# alimentation.net
KiCad netlist of a schematic drawn in Altium Designer
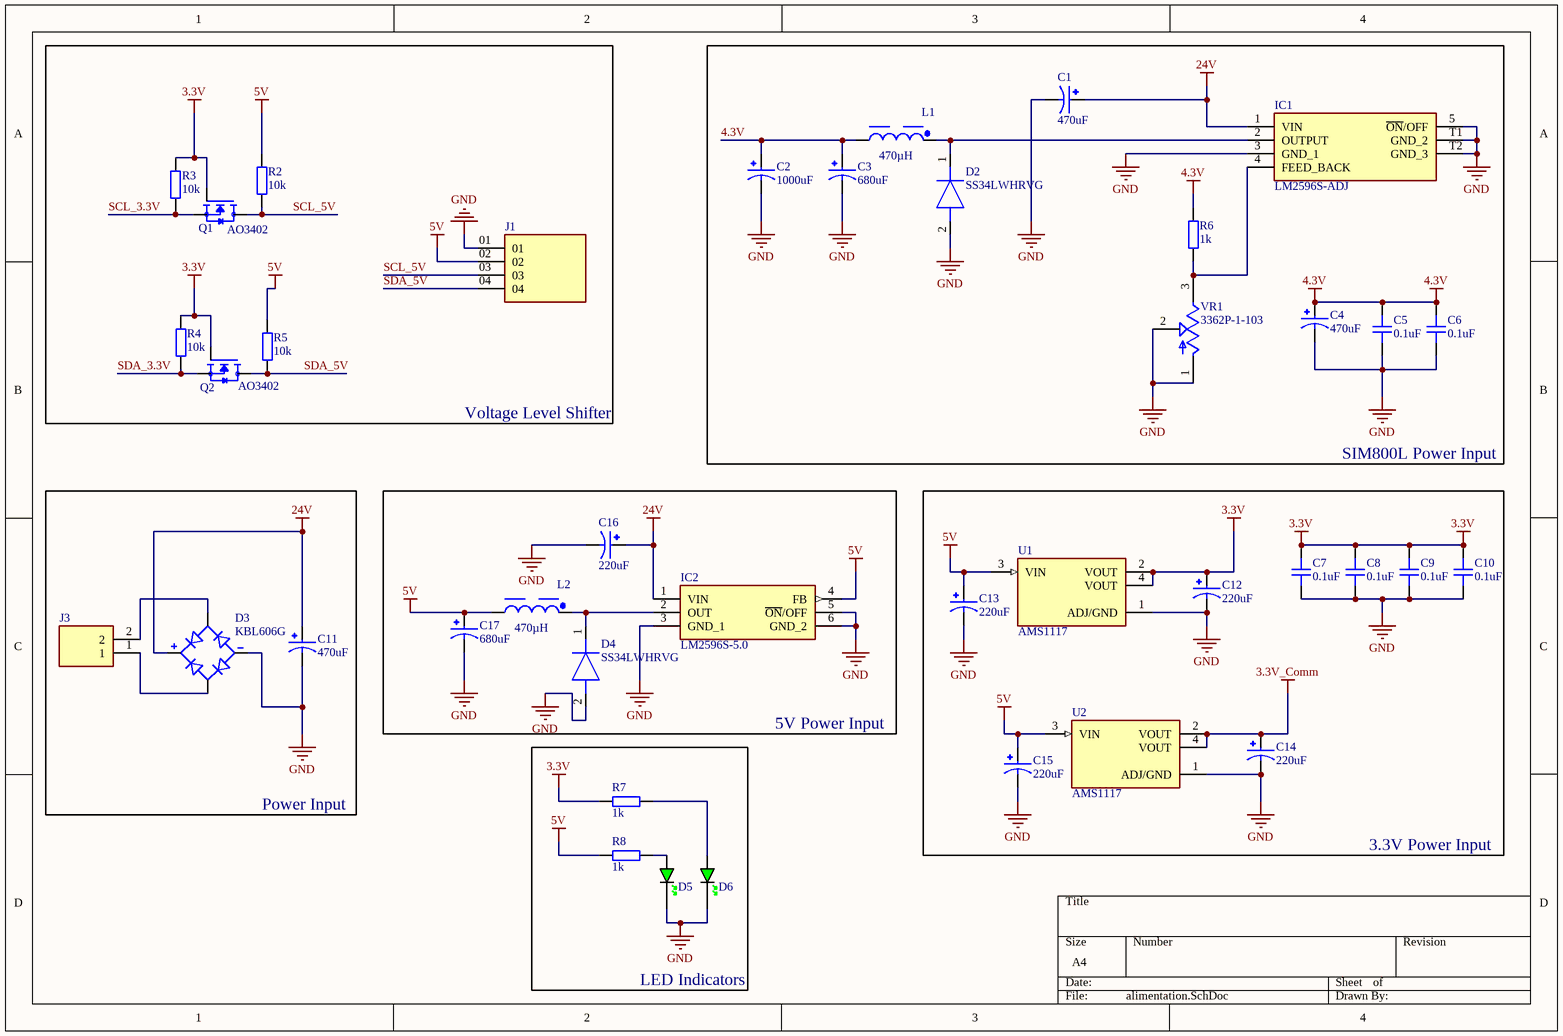
[diagram p0: alimentation.SchDoc]

(export (version "E")
  (design (tool "Eeschema 10.0.6"))
  (components
    (comp (ref "C1")
      (value "470uF")
      (footprint "CAPPRD500W60D1000H1600")
      (description "CAP ALUM 680UF 20% 35V RADIAL")
      (fields (field (name "MF") "Panasonic") (field (name "MP") "EEU-HD1V681B"))
      (libsource (lib "") (part "EEUHD1V681B_1"))
    )
    (comp (ref "C2")
      (value "1000uF")
      (footprint "CAPPRD500W60D1000H2500")
      (description "1000ÂµF 35V Aluminum Electrolytic Capacitors Radial, Can 10000 Hrs @ 105Â°C")
      (fields (field (name "MP") "EEUFS1V102L") (field (name "MF") "Panasonic"))
      (libsource (lib "1000uF 35V capacitor") (part "EEUFS1V102L"))
    )
    (comp (ref "C3")
      (value "680uF")
      (footprint "CAPPRD500W60D1000H1600")
      (description "CAP ALUM 680UF 20% 35V RADIAL")
      (fields (field (name "MF") "Panasonic") (field (name "MP") "EEU-HD1V681B"))
      (libsource (lib "35V 680uF cap") (part "EEUHD1V681B"))
    )
    (comp (ref "C4")
      (value "470uF")
      (footprint "CAPPRD500W60D1000H1600")
      (description "CAP ALUM 680UF 20% 35V RADIAL")
      (fields (field (name "MF") "Panasonic") (field (name "MP") "EEU-HD1V681B"))
      (libsource (lib "35V 680uF cap") (part "EEUHD1V681B"))
    )
    (comp (ref "C5")
      (value "0.1uF")
      (footprint "CAP_0805")
      (description "Capacitor SMD 0805")
      (libsource (lib "Schematic-Lib-PhilsLab") (part "CAP_0805"))
    )
    (comp (ref "C6")
      (value "0.1uF")
      (footprint "CAP_0805")
      (description "Capacitor SMD 0805")
      (libsource (lib "Schematic-Lib-PhilsLab") (part "CAP_0805"))
    )
    (comp (ref "C7")
      (value "0.1uF")
      (footprint "CAP_0805")
      (description "Capacitor SMD 0805")
      (libsource (lib "Schematic-Lib-PhilsLab") (part "CAP_0805"))
    )
    (comp (ref "C8")
      (value "0.1uF")
      (footprint "CAP_0805")
      (description "Capacitor SMD 0805")
      (libsource (lib "Schematic-Lib-PhilsLab") (part "CAP_0805"))
    )
    (comp (ref "C9")
      (value "0.1uF")
      (footprint "CAP_0805")
      (description "Capacitor SMD 0805")
      (libsource (lib "Schematic-Lib-PhilsLab") (part "CAP_0805"))
    )
    (comp (ref "C10")
      (value "0.1uF")
      (footprint "CAP_0805")
      (description "Capacitor SMD 0805")
      (libsource (lib "Schematic-Lib-PhilsLab") (part "CAP_0805"))
    )
    (comp (ref "C11")
      (value "470uF")
      (footprint "CAPPRD500W60D1000H1600")
      (description "CAP ALUM 680UF 20% 35V RADIAL")
      (fields (field (name "MF") "Panasonic") (field (name "MP") "EEU-HD1V681B"))
      (libsource (lib "35V 680uF cap") (part "EEUHD1V681B"))
    )
    (comp (ref "C12")
      (value "220uF")
      (footprint "CAPPRD500W60D800H1150")
      (description "Cap Aluminum 220uF 35V 20% (8 X 11.5mm) Radial 5mm 270mA 1000 hr 105C Ammo Pack")
      (fields (field (name "MP") "EEU-HD1V221B") (field (name "MF") "Panasonic"))
      (libsource (lib "35V 220uF cap") (part "EEUHD1V221B"))
    )
    (comp (ref "C13")
      (value "220uF")
      (footprint "CAPPRD500W60D800H1150")
      (description "Cap Aluminum 220uF 35V 20% (8 X 11.5mm) Radial 5mm 270mA 1000 hr 105C Ammo Pack")
      (fields (field (name "MP") "EEU-HD1V221B") (field (name "MF") "Panasonic"))
      (libsource (lib "35V 220uF cap") (part "EEUHD1V221B"))
    )
    (comp (ref "C14")
      (value "220uF")
      (footprint "CAPPRD500W60D800H1150")
      (description "Cap Aluminum 220uF 35V 20% (8 X 11.5mm) Radial 5mm 270mA 1000 hr 105C Ammo Pack")
      (fields (field (name "MP") "EEU-HD1V221B") (field (name "MF") "Panasonic"))
      (libsource (lib "35V 220uF cap") (part "EEUHD1V221B"))
    )
    (comp (ref "C15")
      (value "220uF")
      (footprint "CAPPRD500W60D800H1150")
      (description "Cap Aluminum 220uF 35V 20% (8 X 11.5mm) Radial 5mm 270mA 1000 hr 105C Ammo Pack")
      (fields (field (name "MP") "EEU-HD1V221B") (field (name "MF") "Panasonic"))
      (libsource (lib "35V 220uF cap") (part "EEUHD1V221B"))
    )
    (comp (ref "C16")
      (value "220uF")
      (footprint "CAPPRD500W60D800H1150")
      (description "Cap Aluminum 220uF 35V 20% (8 X 11.5mm) Radial 5mm 270mA 1000 hr 105C Ammo Pack")
      (fields (field (name "MP") "EEU-HD1V221B") (field (name "MF") "Panasonic"))
      (libsource (lib "") (part "EEUHD1V221B_1"))
    )
    (comp (ref "C17")
      (value "680uF")
      (footprint "CAPPRD500W60D1000H1600")
      (description "CAP ALUM 680UF 20% 35V RADIAL")
      (fields (field (name "MF") "Panasonic") (field (name "MP") "EEU-HD1V681B"))
      (libsource (lib "35V 680uF cap") (part "EEUHD1V681B"))
    )
    (comp (ref "D2")
      (value "SS34LWHRVG")
      (footprint "SamacSys:SODFL3718X102N")
      (description "Diode")
      (fields (field (name "MOUSER PART NUMBER") "821-SS34LWHRVG"))
      (libsource (lib "*") (part "SS34LWHRVG"))
    )
    (comp (ref "D3")
      (value "KBL606G")
      (footprint "SIP600W130P510L1900H1630Q4")
      (libsource (lib "KBL606G") (part "KBL606G"))
    )
    (comp (ref "D4")
      (value "SS34LWHRVG")
      (footprint "SamacSys:SODFL3718X102N")
      (description "Diode")
      (fields (field (name "MOUSER PART NUMBER") "821-SS34LWHRVG"))
      (libsource (lib "*") (part "SS34LWHRVG"))
    )
    (comp (ref "D5")
      (value "GREEN")
      (footprint "LED_0805_GREEN")
      (description "LED 0805 GREEN SMD")
      (libsource (lib "Schematic-Lib-PhilsLab") (part "LED_0805_GREEN"))
    )
    (comp (ref "D6")
      (value "GREEN")
      (footprint "LED_0805_GREEN")
      (description "LED 0805 GREEN SMD")
      (libsource (lib "Schematic-Lib-PhilsLab") (part "LED_0805_GREEN"))
    )
    (comp (ref "IC1")
      (value "LM2596S-ADJ")
      (footprint "SamacSys:LM2596SXADJ")
      (description "Integrated Circuit")
      (fields (field (name "MOUSER PART NUMBER") "926-LM2596S-ADJ"))
      (libsource (lib "*") (part "LM2596S-ADJ"))
    )
    (comp (ref "IC2")
      (value "LM2596S-5.0")
      (footprint "SamacSys:KTT0005B")
      (description "Integrated Circuit")
      (fields (field (name "MOUSER PART NUMBER") "926-LM2596S-50"))
      (libsource (lib "*") (part "LM2596S-5.0"))
    )
    (comp (ref "J1")
      (value "MTSW-104-08-S-S-270")
      (footprint "SAMTEC_MTSW-104-08-S-S-270")
      (description "Connector Header Through Hole 4 position 0.100 (2.54mm)")
      (fields (field (name "MF") "Samtec"))
      (libsource (lib "TH 4 pins header") (part "MTSW-104-08-S-S-270"))
    )
    (comp (ref "J3")
      (value "TBP04R12-500-02BE")
      (footprint "CUI_TBP04R12-500-02BE")
      (description "2~24 Poles, Pluggable, Receptacle, Horizontal, 5.0 Pitch, Terminal Block Connector")
      (fields (field (name "MF") "Same Sky"))
      (libsource (lib "TBP04R12-500-02BE") (part "TBP04R12-500-02BE"))
    )
    (comp (ref "L1")
      (value "470µH")
      (footprint "WE-PD HV_1210")
      (description "WE-PD HV High Voltage Power Inductor, SMT, size 1210, 1000µH, 0.72A, 1.4Ω")
      (fields
        (field (name "MANUFACTURER PART NUMBER") "7687709102")
        (field (name "MANUFACTURER") "Wurth Elektronik")
      )
      (libsource (lib "inductors") (part "7687709102"))
    )
    (comp (ref "L2")
      (value "470µH")
      (footprint "WE-PD HV_1210")
      (description "WE-PD HV High Voltage Power Inductor, SMT, size 1210, 1000µH, 0.72A, 1.4Ω")
      (fields
        (field (name "MANUFACTURER PART NUMBER") "7687709102")
        (field (name "MANUFACTURER") "Wurth Elektronik")
      )
      (libsource (lib "inductors") (part "7687709102"))
    )
    (comp (ref "Q1")
      (value "AO3402")
      (footprint "SOT95P280X125-3N")
      (description "N-Channel 30 V 4A (Ta) 1.4W (Ta) Surface Mount SOT-23-3")
      (fields (field (name "MF") "Alpha & Omega Semiconductor"))
      (libsource (lib "AO3402") (part "AO3402"))
    )
    (comp (ref "Q2")
      (value "AO3402")
      (footprint "SOT95P280X125-3N")
      (description "N-Channel 30 V 4A (Ta) 1.4W (Ta) Surface Mount SOT-23-3")
      (fields (field (name "MF") "Alpha & Omega Semiconductor"))
      (libsource (lib "AO3402") (part "AO3402"))
    )
    (comp (ref "R2")
      (value "10k")
      (footprint "RES_1206")
      (description "Resistor SMD 1206")
      (libsource (lib "Schematic-Lib-PhilsLab") (part "RES_1206"))
    )
    (comp (ref "R3")
      (value "10k")
      (footprint "RES_1206")
      (description "Resistor SMD 1206")
      (libsource (lib "Schematic-Lib-PhilsLab") (part "RES_1206"))
    )
    (comp (ref "R4")
      (value "10k")
      (footprint "RES_1206")
      (description "Resistor SMD 1206")
      (libsource (lib "Schematic-Lib-PhilsLab") (part "RES_1206"))
    )
    (comp (ref "R5")
      (value "10k")
      (footprint "RES_1206")
      (description "Resistor SMD 1206")
      (libsource (lib "Schematic-Lib-PhilsLab") (part "RES_1206"))
    )
    (comp (ref "R6")
      (value "1k")
      (footprint "RES_1206")
      (description "Resistor SMD 1206")
      (libsource (lib "Schematic-Lib-PhilsLab") (part "RES_1206"))
    )
    (comp (ref "R7")
      (value "1k")
      (footprint "RES_1206")
      (description "Resistor SMD 1206")
      (libsource (lib "Schematic-Lib-PhilsLab") (part "RES_1206"))
    )
    (comp (ref "R8")
      (value "1k")
      (footprint "RES_1206")
      (description "Resistor SMD 1206")
      (libsource (lib "Schematic-Lib-PhilsLab") (part "RES_1206"))
    )
    (comp (ref "U1")
      (value "AMS1117")
      (footprint "SOT229P700X180-4N")
      (description "1A LOW DROPOUT VOLTAGE REGULATOR SOT-223")
      (fields (field (name "MF") "Advanced Monolithic Systems"))
      (libsource (lib "AMS1117") (part "AMS1117"))
    )
    (comp (ref "U2")
      (value "AMS1117")
      (footprint "SOT229P700X180-4N")
      (description "1A LOW DROPOUT VOLTAGE REGULATOR SOT-223")
      (fields (field (name "MF") "Advanced Monolithic Systems"))
      (libsource (lib "AMS1117") (part "AMS1117"))
    )
    (comp (ref "VR1")
      (value "3362P-1-103")
      (footprint "TRIM_3362P-1-103:TRIM_3362P-1-103")
      (description "TRIMMER - 1/4in SQ ST CERMET ¦ Bourns 3362P-1-103")
      (fields (field (name "MF") "Bourns"))
      (libsource (lib "3362P-1-103") (part "3362P-1-103"))
    )
  )
  (nets
    (net (code "1") (name "/SCL_3.3V") (class "Default")
      (node (ref "Q1") (pin "2") (pinfunction "S_2") (pintype "passive"))
      (node (ref "R3") (pin "2") (pinfunction "2_2") (pintype "passive"))
    )
    (net (code "2") (name "/SCL_5V") (class "Default")
      (node (ref "J1") (pin "03") (pinfunction "03_03") (pintype "passive"))
      (node (ref "Q1") (pin "3") (pinfunction "D_3") (pintype "passive"))
      (node (ref "R2") (pin "2") (pinfunction "2_2") (pintype "passive"))
    )
    (net (code "3") (name "/SDA_3.3V") (class "Default")
      (node (ref "Q2") (pin "2") (pinfunction "S_2") (pintype "passive"))
      (node (ref "R4") (pin "2") (pinfunction "2_2") (pintype "passive"))
    )
    (net (code "4") (name "/SDA_5V") (class "Default")
      (node (ref "J1") (pin "04") (pinfunction "04_04") (pintype "passive"))
      (node (ref "Q2") (pin "3") (pinfunction "D_3") (pintype "passive"))
      (node (ref "R5") (pin "2") (pinfunction "2_2") (pintype "passive"))
    )
    (net (code "5") (name "3.3V") (class "Default")
      (node (ref "C10") (pin "2") (pinfunction "2_2") (pintype "passive"))
      (node (ref "C12") (pin "P") (pinfunction "P_P") (pintype "passive"))
      (node (ref "C7") (pin "2") (pinfunction "2_2") (pintype "passive"))
      (node (ref "C8") (pin "2") (pinfunction "2_2") (pintype "passive"))
      (node (ref "C9") (pin "2") (pinfunction "2_2") (pintype "passive"))
      (node (ref "Q1") (pin "1") (pinfunction "G_1") (pintype "passive"))
      (node (ref "Q2") (pin "1") (pinfunction "G_1") (pintype "passive"))
      (node (ref "R3") (pin "1") (pinfunction "1_1") (pintype "passive"))
      (node (ref "R4") (pin "1") (pinfunction "1_1") (pintype "passive"))
      (node (ref "R7") (pin "1") (pinfunction "1_1") (pintype "passive"))
      (node (ref "U1") (pin "2") (pinfunction "VOUT_2") (pintype "power_in"))
      (node (ref "U1") (pin "4") (pinfunction "VOUT_4") (pintype "power_in"))
    )
    (net (code "6") (name "3.3V_Comm") (class "Default")
      (node (ref "C14") (pin "P") (pinfunction "P_P") (pintype "passive"))
      (node (ref "U2") (pin "2") (pinfunction "VOUT_2") (pintype "power_in"))
      (node (ref "U2") (pin "4") (pinfunction "VOUT_4") (pintype "power_in"))
    )
    (net (code "7") (name "4.3V") (class "Default")
      (node (ref "C2") (pin "P") (pinfunction "P_P") (pintype "passive"))
      (node (ref "C3") (pin "P") (pinfunction "P_P") (pintype "passive"))
      (node (ref "C4") (pin "P") (pinfunction "P_P") (pintype "passive"))
      (node (ref "C5") (pin "2") (pinfunction "2_2") (pintype "passive"))
      (node (ref "C6") (pin "2") (pinfunction "2_2") (pintype "passive"))
      (node (ref "L1") (pin "2") (pinfunction "2_2") (pintype "passive"))
      (node (ref "R6") (pin "2") (pinfunction "2_2") (pintype "passive"))
    )
    (net (code "8") (name "5V") (class "Default")
      (node (ref "C13") (pin "P") (pinfunction "P_P") (pintype "passive"))
      (node (ref "C15") (pin "P") (pinfunction "P_P") (pintype "passive"))
      (node (ref "C17") (pin "P") (pinfunction "P_P") (pintype "passive"))
      (node (ref "IC2") (pin "4") (pinfunction "FB_4") (pintype "output"))
      (node (ref "J1") (pin "02") (pinfunction "02_02") (pintype "passive"))
      (node (ref "L2") (pin "2") (pinfunction "2_2") (pintype "passive"))
      (node (ref "R2") (pin "1") (pinfunction "1_1") (pintype "passive"))
      (node (ref "R5") (pin "1") (pinfunction "1_1") (pintype "passive"))
      (node (ref "R8") (pin "1") (pinfunction "1_1") (pintype "passive"))
      (node (ref "U1") (pin "3") (pinfunction "VIN_3") (pintype "input"))
      (node (ref "U2") (pin "3") (pinfunction "VIN_3") (pintype "input"))
    )
    (net (code "9") (name "24V") (class "Default")
      (node (ref "C1") (pin "P") (pinfunction "P_P") (pintype "passive"))
      (node (ref "C11") (pin "P") (pinfunction "P_P") (pintype "passive"))
      (node (ref "C16") (pin "P") (pinfunction "P_P") (pintype "passive"))
      (node (ref "D3") (pin "POS") (pinfunction "POS_POS") (pintype "passive"))
      (node (ref "IC1") (pin "1") (pinfunction "VIN_1") (pintype "passive"))
      (node (ref "IC2") (pin "1") (pinfunction "VIN_1") (pintype "passive"))
    )
    (net (code "10") (name "GND") (class "Default")
      (node (ref "C1") (pin "N") (pinfunction "N_N") (pintype "passive"))
      (node (ref "C10") (pin "1") (pinfunction "1_1") (pintype "passive"))
      (node (ref "C11") (pin "N") (pinfunction "N_N") (pintype "passive"))
      (node (ref "C12") (pin "N") (pinfunction "N_N") (pintype "passive"))
      (node (ref "C13") (pin "N") (pinfunction "N_N") (pintype "passive"))
      (node (ref "C14") (pin "N") (pinfunction "N_N") (pintype "passive"))
      (node (ref "C15") (pin "N") (pinfunction "N_N") (pintype "passive"))
      (node (ref "C16") (pin "N") (pinfunction "N_N") (pintype "passive"))
      (node (ref "C17") (pin "N") (pinfunction "N_N") (pintype "passive"))
      (node (ref "C2") (pin "N") (pinfunction "N_N") (pintype "passive"))
      (node (ref "C3") (pin "N") (pinfunction "N_N") (pintype "passive"))
      (node (ref "C4") (pin "N") (pinfunction "N_N") (pintype "passive"))
      (node (ref "C5") (pin "1") (pinfunction "1_1") (pintype "passive"))
      (node (ref "C6") (pin "1") (pinfunction "1_1") (pintype "passive"))
      (node (ref "C7") (pin "1") (pinfunction "1_1") (pintype "passive"))
      (node (ref "C8") (pin "1") (pinfunction "1_1") (pintype "passive"))
      (node (ref "C9") (pin "1") (pinfunction "1_1") (pintype "passive"))
      (node (ref "D2") (pin "2") (pinfunction "A_2") (pintype "passive"))
      (node (ref "D3") (pin "NEG") (pinfunction "NEG_NEG") (pintype "passive"))
      (node (ref "D4") (pin "2") (pinfunction "A_2") (pintype "passive"))
      (node (ref "D5") (pin "K") (pinfunction "K_K") (pintype "passive"))
      (node (ref "D6") (pin "K") (pinfunction "K_K") (pintype "passive"))
      (node (ref "IC1") (pin "3") (pinfunction "GND_1_3") (pintype "passive"))
      (node (ref "IC1") (pin "5") (pinfunction "~{ON}/OFF_5") (pintype "passive"))
      (node (ref "IC1") (pin "T1") (pinfunction "GND_2_T1") (pintype "passive"))
      (node (ref "IC1") (pin "T2") (pinfunction "GND_3_T2") (pintype "passive"))
      (node (ref "IC2") (pin "3") (pinfunction "GND_1_3") (pintype "passive"))
      (node (ref "IC2") (pin "5") (pinfunction "~{ON}/OFF_5") (pintype "passive"))
      (node (ref "IC2") (pin "6") (pinfunction "GND_2_6") (pintype "passive"))
      (node (ref "J1") (pin "01") (pinfunction "01_01") (pintype "passive"))
      (node (ref "U1") (pin "1") (pinfunction "ADJ/GND_1") (pintype "power_in"))
      (node (ref "U2") (pin "1") (pinfunction "ADJ/GND_1") (pintype "power_in"))
      (node (ref "VR1") (pin "1") (pinfunction "CCW_1") (pintype "passive"))
      (node (ref "VR1") (pin "2") (pinfunction "WIPER_2") (pintype "passive"))
    )
    (net (code "11") (name "Net-(D2-K)") (class "Default")
      (node (ref "D2") (pin "1") (pinfunction "K_1") (pintype "passive"))
      (node (ref "IC1") (pin "2") (pinfunction "OUTPUT_2") (pintype "passive"))
      (node (ref "L1") (pin "1") (pinfunction "1_1") (pintype "passive"))
    )
    (net (code "12") (name "Net-(D3-PadAC1)") (class "Default")
      (node (ref "D3") (pin "AC1") (pinfunction "AC1_AC1") (pintype "passive"))
      (node (ref "J3") (pin "2") (pinfunction "2_2") (pintype "passive"))
    )
    (net (code "13") (name "Net-(D3-PadAC2)") (class "Default")
      (node (ref "D3") (pin "AC2") (pinfunction "AC2_AC2") (pintype "passive"))
      (node (ref "J3") (pin "1") (pinfunction "1_1") (pintype "passive"))
    )
    (net (code "14") (name "Net-(D4-K)") (class "Default")
      (node (ref "D4") (pin "1") (pinfunction "K_1") (pintype "passive"))
      (node (ref "IC2") (pin "2") (pinfunction "OUT_2") (pintype "passive"))
      (node (ref "L2") (pin "1") (pinfunction "1_1") (pintype "passive"))
    )
    (net (code "15") (name "Net-(D5-PadA)") (class "Default")
      (node (ref "D5") (pin "A") (pinfunction "A_A") (pintype "passive"))
      (node (ref "R8") (pin "2") (pinfunction "2_2") (pintype "passive"))
    )
    (net (code "16") (name "Net-(D6-PadA)") (class "Default")
      (node (ref "D6") (pin "A") (pinfunction "A_A") (pintype "passive"))
      (node (ref "R7") (pin "2") (pinfunction "2_2") (pintype "passive"))
    )
    (net (code "17") (name "Net-(IC1-FEED_BACK)") (class "Default")
      (node (ref "IC1") (pin "4") (pinfunction "FEED_BACK_4") (pintype "passive"))
      (node (ref "R6") (pin "1") (pinfunction "1_1") (pintype "passive"))
      (node (ref "VR1") (pin "3") (pinfunction "CW_3") (pintype "passive"))
    )
  )
)
